# RJ45.net
KiCad netlist of a schematic drawn in Altium Designer
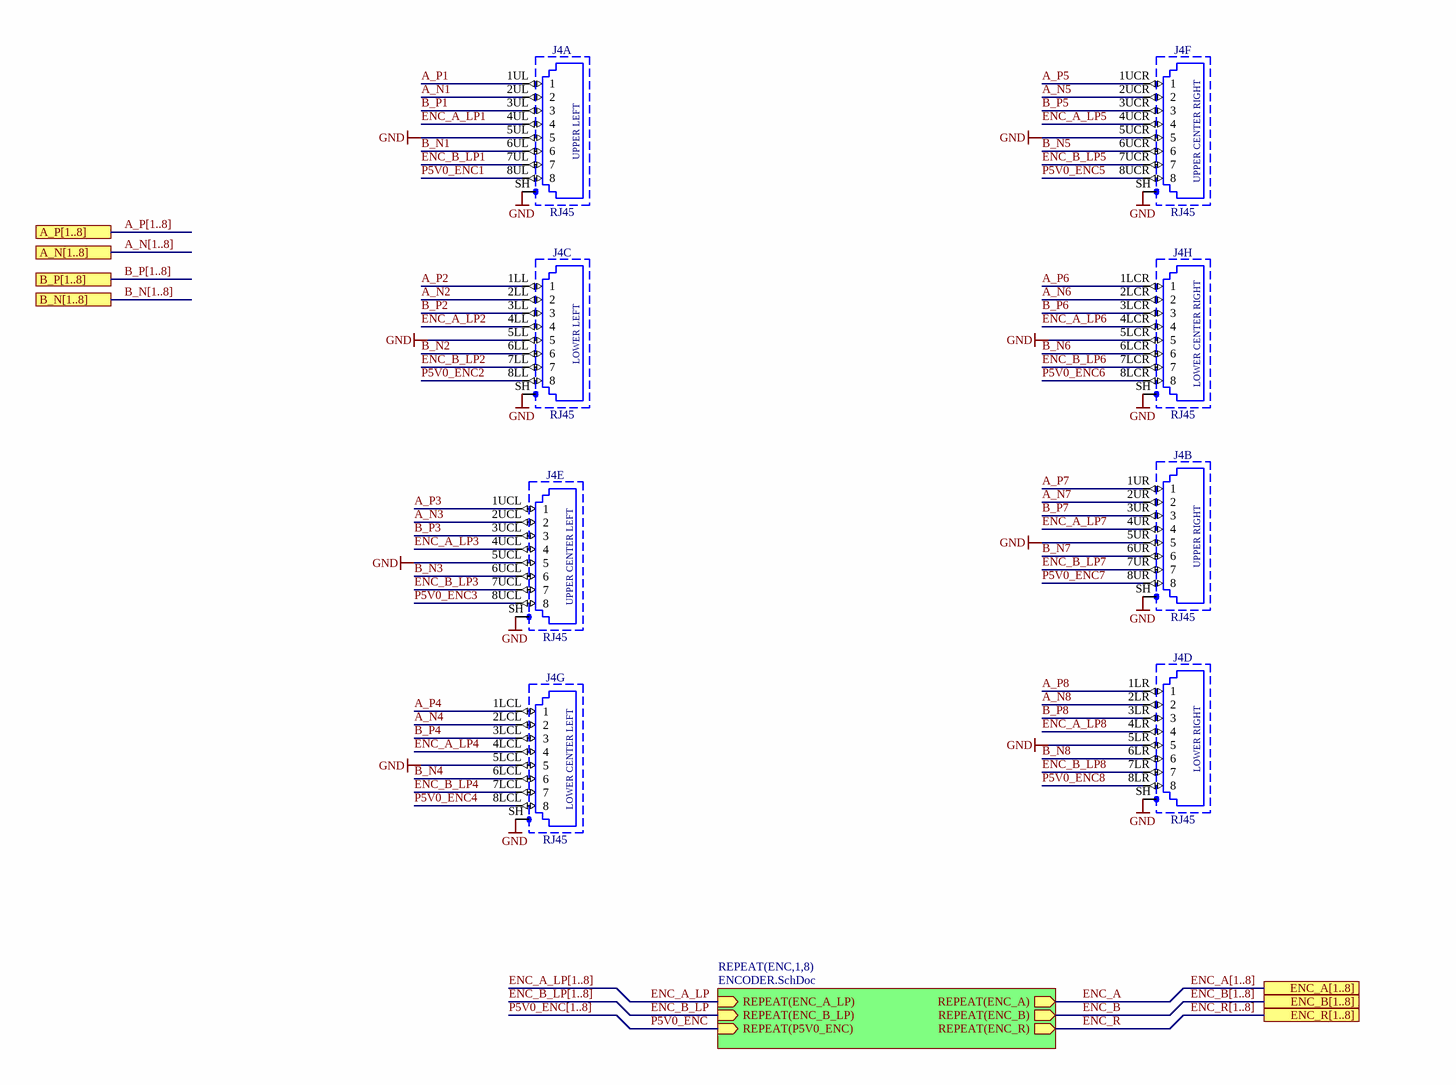
[diagram p0: RJ45.SchDoc, left]
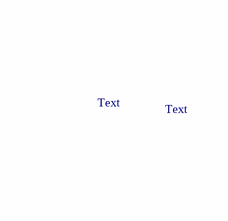
[diagram p1: RJ45.SchDoc, right]

(export (version "E")
  (design (tool "Eeschema 10.0.6"))
  (components
    (comp (ref "J4")
      (value "RJ45")
      (footprint "TYCO_5569262-1")
      (description "Connector 2 x 4 RJ45 + Shield")
      (fields
        (field (name "PART NUMBER") "TYCO_5569262-1")
        (field (name "MANUFACTURER") "TYCO ELECTRONICS")
        (field (name "AUTHOR") "CERN DEM MR")
      )
      (libsource (lib "Connectors") (part "Connector 2 x 4 RJ45 + Shield"))
    )
  )
  (nets
    (net (code "25") (name "/A_N1") (class "Default")
      (node (ref "J4") (pin "2UL") (pinfunction "2_2UL") (pintype "bidirectional"))
    )
    (net (code "26") (name "/A_N2") (class "Default")
      (node (ref "J4") (pin "2LL") (pinfunction "2_2LL") (pintype "bidirectional"))
    )
    (net (code "27") (name "/A_N3") (class "Default")
      (node (ref "J4") (pin "2UCL") (pinfunction "2_2UCL") (pintype "bidirectional"))
    )
    (net (code "28") (name "/A_N4") (class "Default")
      (node (ref "J4") (pin "2LCL") (pinfunction "2_2LCL") (pintype "bidirectional"))
    )
    (net (code "29") (name "/A_N5") (class "Default")
      (node (ref "J4") (pin "2UCR") (pinfunction "2_2UCR") (pintype "bidirectional"))
    )
    (net (code "30") (name "/A_N6") (class "Default")
      (node (ref "J4") (pin "2LCR") (pinfunction "2_2LCR") (pintype "bidirectional"))
    )
    (net (code "31") (name "/A_N7") (class "Default")
      (node (ref "J4") (pin "2UR") (pinfunction "2_2UR") (pintype "bidirectional"))
    )
    (net (code "32") (name "/A_N8") (class "Default")
      (node (ref "J4") (pin "2LR") (pinfunction "2_2LR") (pintype "bidirectional"))
    )
    (net (code "34") (name "/A_P1") (class "Default")
      (node (ref "J4") (pin "1UL") (pinfunction "1_1UL") (pintype "bidirectional"))
    )
    (net (code "35") (name "/A_P2") (class "Default")
      (node (ref "J4") (pin "1LL") (pinfunction "1_1LL") (pintype "bidirectional"))
    )
    (net (code "36") (name "/A_P3") (class "Default")
      (node (ref "J4") (pin "1UCL") (pinfunction "1_1UCL") (pintype "bidirectional"))
    )
    (net (code "37") (name "/A_P4") (class "Default")
      (node (ref "J4") (pin "1LCL") (pinfunction "1_1LCL") (pintype "bidirectional"))
    )
    (net (code "38") (name "/A_P5") (class "Default")
      (node (ref "J4") (pin "1UCR") (pinfunction "1_1UCR") (pintype "bidirectional"))
    )
    (net (code "39") (name "/A_P6") (class "Default")
      (node (ref "J4") (pin "1LCR") (pinfunction "1_1LCR") (pintype "bidirectional"))
    )
    (net (code "40") (name "/A_P7") (class "Default")
      (node (ref "J4") (pin "1UR") (pinfunction "1_1UR") (pintype "bidirectional"))
    )
    (net (code "41") (name "/A_P8") (class "Default")
      (node (ref "J4") (pin "1LR") (pinfunction "1_1LR") (pintype "bidirectional"))
    )
    (net (code "43") (name "/B_N1") (class "Default")
      (node (ref "J4") (pin "6UL") (pinfunction "6_6UL") (pintype "bidirectional"))
    )
    (net (code "44") (name "/B_N2") (class "Default")
      (node (ref "J4") (pin "6LL") (pinfunction "6_6LL") (pintype "bidirectional"))
    )
    (net (code "45") (name "/B_N3") (class "Default")
      (node (ref "J4") (pin "6UCL") (pinfunction "6_6UCL") (pintype "bidirectional"))
    )
    (net (code "46") (name "/B_N4") (class "Default")
      (node (ref "J4") (pin "6LCL") (pinfunction "6_6LCL") (pintype "bidirectional"))
    )
    (net (code "47") (name "/B_N5") (class "Default")
      (node (ref "J4") (pin "6UCR") (pinfunction "6_6UCR") (pintype "bidirectional"))
    )
    (net (code "48") (name "/B_N6") (class "Default")
      (node (ref "J4") (pin "6LCR") (pinfunction "6_6LCR") (pintype "bidirectional"))
    )
    (net (code "49") (name "/B_N7") (class "Default")
      (node (ref "J4") (pin "6UR") (pinfunction "6_6UR") (pintype "bidirectional"))
    )
    (net (code "50") (name "/B_N8") (class "Default")
      (node (ref "J4") (pin "6LR") (pinfunction "6_6LR") (pintype "bidirectional"))
    )
    (net (code "52") (name "/B_P1") (class "Default")
      (node (ref "J4") (pin "3UL") (pinfunction "3_3UL") (pintype "bidirectional"))
    )
    (net (code "53") (name "/B_P2") (class "Default")
      (node (ref "J4") (pin "3LL") (pinfunction "3_3LL") (pintype "bidirectional"))
    )
    (net (code "54") (name "/B_P3") (class "Default")
      (node (ref "J4") (pin "3UCL") (pinfunction "3_3UCL") (pintype "bidirectional"))
    )
    (net (code "55") (name "/B_P4") (class "Default")
      (node (ref "J4") (pin "3LCL") (pinfunction "3_3LCL") (pintype "bidirectional"))
    )
    (net (code "56") (name "/B_P5") (class "Default")
      (node (ref "J4") (pin "3UCR") (pinfunction "3_3UCR") (pintype "bidirectional"))
    )
    (net (code "57") (name "/B_P6") (class "Default")
      (node (ref "J4") (pin "3LCR") (pinfunction "3_3LCR") (pintype "bidirectional"))
    )
    (net (code "58") (name "/B_P7") (class "Default")
      (node (ref "J4") (pin "3UR") (pinfunction "3_3UR") (pintype "bidirectional"))
    )
    (net (code "59") (name "/B_P8") (class "Default")
      (node (ref "J4") (pin "3LR") (pinfunction "3_3LR") (pintype "bidirectional"))
    )
    (net (code "64") (name "/ENC_A_LP1") (class "Default")
      (node (ref "J4") (pin "4UL") (pinfunction "4_4UL") (pintype "bidirectional"))
    )
    (net (code "65") (name "/ENC_A_LP2") (class "Default")
      (node (ref "J4") (pin "4LL") (pinfunction "4_4LL") (pintype "bidirectional"))
    )
    (net (code "66") (name "/ENC_A_LP3") (class "Default")
      (node (ref "J4") (pin "4UCL") (pinfunction "4_4UCL") (pintype "bidirectional"))
    )
    (net (code "67") (name "/ENC_A_LP4") (class "Default")
      (node (ref "J4") (pin "4LCL") (pinfunction "4_4LCL") (pintype "bidirectional"))
    )
    (net (code "68") (name "/ENC_A_LP5") (class "Default")
      (node (ref "J4") (pin "4UCR") (pinfunction "4_4UCR") (pintype "bidirectional"))
    )
    (net (code "69") (name "/ENC_A_LP6") (class "Default")
      (node (ref "J4") (pin "4LCR") (pinfunction "4_4LCR") (pintype "bidirectional"))
    )
    (net (code "70") (name "/ENC_A_LP7") (class "Default")
      (node (ref "J4") (pin "4UR") (pinfunction "4_4UR") (pintype "bidirectional"))
    )
    (net (code "71") (name "/ENC_A_LP8") (class "Default")
      (node (ref "J4") (pin "4LR") (pinfunction "4_4LR") (pintype "bidirectional"))
    )
    (net (code "76") (name "/ENC_B_LP1") (class "Default")
      (node (ref "J4") (pin "7UL") (pinfunction "7_7UL") (pintype "bidirectional"))
    )
    (net (code "77") (name "/ENC_B_LP2") (class "Default")
      (node (ref "J4") (pin "7LL") (pinfunction "7_7LL") (pintype "bidirectional"))
    )
    (net (code "78") (name "/ENC_B_LP3") (class "Default")
      (node (ref "J4") (pin "7UCL") (pinfunction "7_7UCL") (pintype "bidirectional"))
    )
    (net (code "79") (name "/ENC_B_LP4") (class "Default")
      (node (ref "J4") (pin "7LCL") (pinfunction "7_7LCL") (pintype "bidirectional"))
    )
    (net (code "80") (name "/ENC_B_LP5") (class "Default")
      (node (ref "J4") (pin "7UCR") (pinfunction "7_7UCR") (pintype "bidirectional"))
    )
    (net (code "81") (name "/ENC_B_LP6") (class "Default")
      (node (ref "J4") (pin "7LCR") (pinfunction "7_7LCR") (pintype "bidirectional"))
    )
    (net (code "82") (name "/ENC_B_LP7") (class "Default")
      (node (ref "J4") (pin "7UR") (pinfunction "7_7UR") (pintype "bidirectional"))
    )
    (net (code "83") (name "/ENC_B_LP8") (class "Default")
      (node (ref "J4") (pin "7LR") (pinfunction "7_7LR") (pintype "bidirectional"))
    )
    (net (code "88") (name "/P5V0_ENC1") (class "Default")
      (node (ref "J4") (pin "8UL") (pinfunction "8_8UL") (pintype "bidirectional"))
    )
    (net (code "89") (name "/P5V0_ENC2") (class "Default")
      (node (ref "J4") (pin "8LL") (pinfunction "8_8LL") (pintype "bidirectional"))
    )
    (net (code "90") (name "/P5V0_ENC3") (class "Default")
      (node (ref "J4") (pin "8UCL") (pinfunction "8_8UCL") (pintype "bidirectional"))
    )
    (net (code "91") (name "/P5V0_ENC4") (class "Default")
      (node (ref "J4") (pin "8LCL") (pinfunction "8_8LCL") (pintype "bidirectional"))
    )
    (net (code "92") (name "/P5V0_ENC5") (class "Default")
      (node (ref "J4") (pin "8UCR") (pinfunction "8_8UCR") (pintype "bidirectional"))
    )
    (net (code "93") (name "/P5V0_ENC6") (class "Default")
      (node (ref "J4") (pin "8LCR") (pinfunction "8_8LCR") (pintype "bidirectional"))
    )
    (net (code "94") (name "/P5V0_ENC7") (class "Default")
      (node (ref "J4") (pin "8UR") (pinfunction "8_8UR") (pintype "bidirectional"))
    )
    (net (code "95") (name "/P5V0_ENC8") (class "Default")
      (node (ref "J4") (pin "8LR") (pinfunction "8_8LR") (pintype "bidirectional"))
    )
    (net (code "97") (name "GND") (class "Default")
      (node (ref "J4") (pin "5LCL") (pinfunction "5_5LCL") (pintype "bidirectional"))
      (node (ref "J4") (pin "5LCR") (pinfunction "5_5LCR") (pintype "bidirectional"))
      (node (ref "J4") (pin "5LL") (pinfunction "5_5LL") (pintype "bidirectional"))
      (node (ref "J4") (pin "5LR") (pinfunction "5_5LR") (pintype "bidirectional"))
      (node (ref "J4") (pin "5UCL") (pinfunction "5_5UCL") (pintype "bidirectional"))
      (node (ref "J4") (pin "5UCR") (pinfunction "5_5UCR") (pintype "bidirectional"))
      (node (ref "J4") (pin "5UL") (pinfunction "5_5UL") (pintype "bidirectional"))
      (node (ref "J4") (pin "5UR") (pinfunction "5_5UR") (pintype "bidirectional"))
      (node (ref "J4") (pin "SH") (pinfunction "1_SH") (pintype "passive"))
    )
  )
)
